# Motherboard_Rev_A.net
KiCad netlist of a schematic drawn in EAGLE
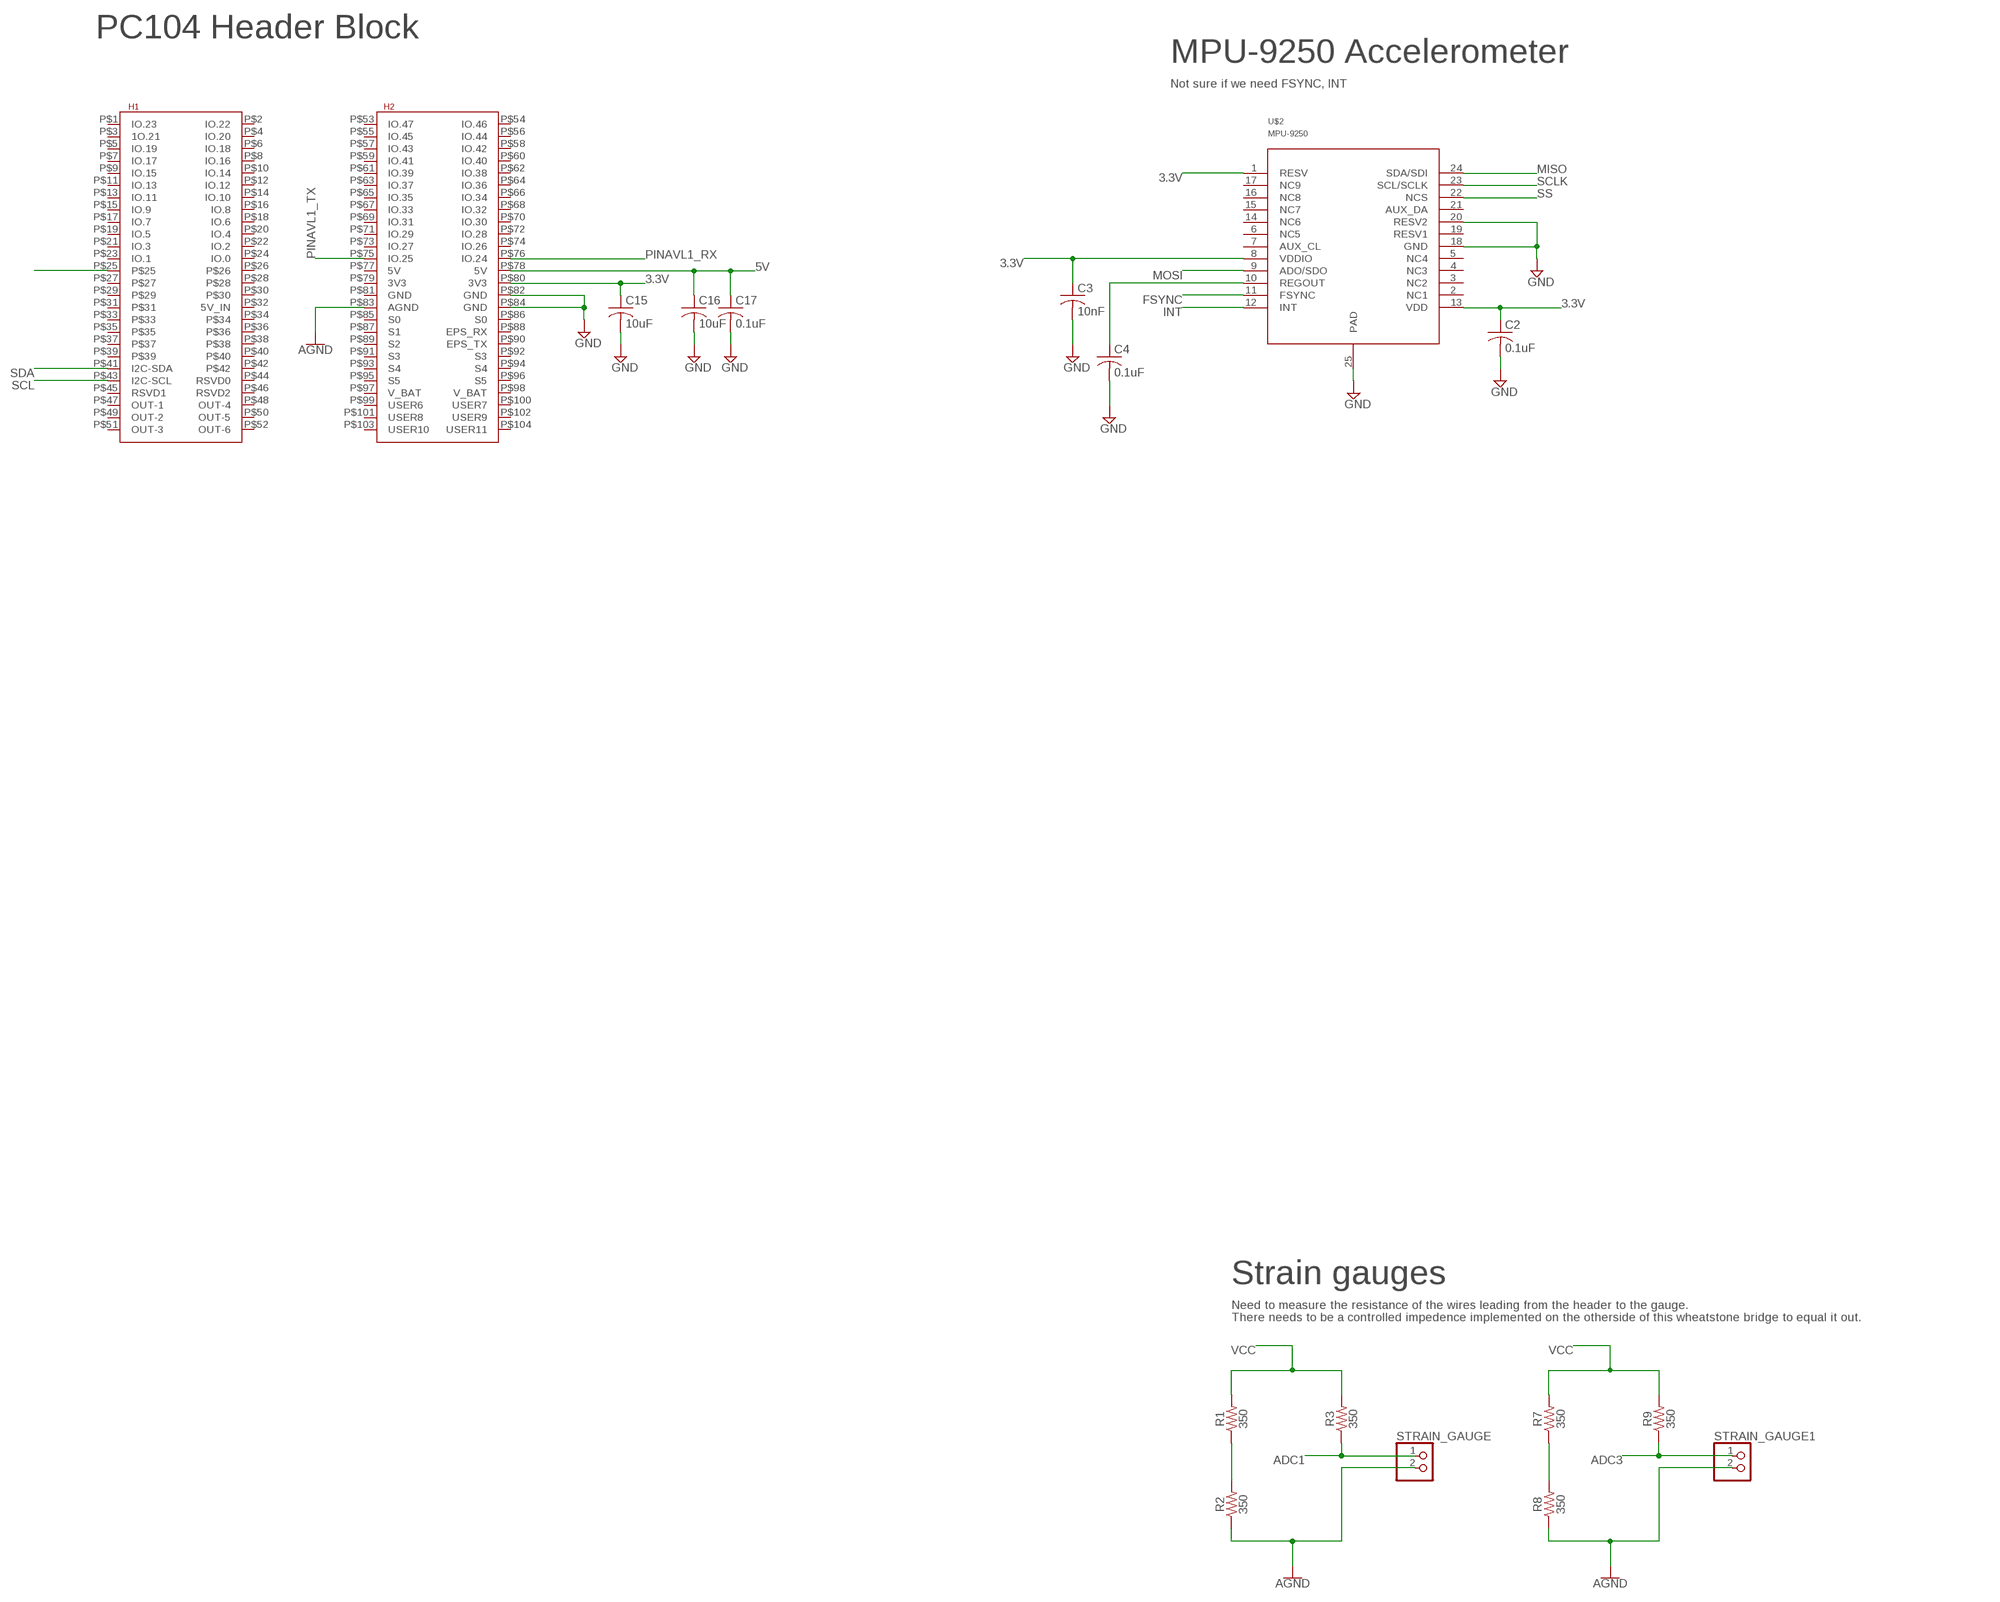
[diagram p0: schematic, sheet 1, part 1 of 2]
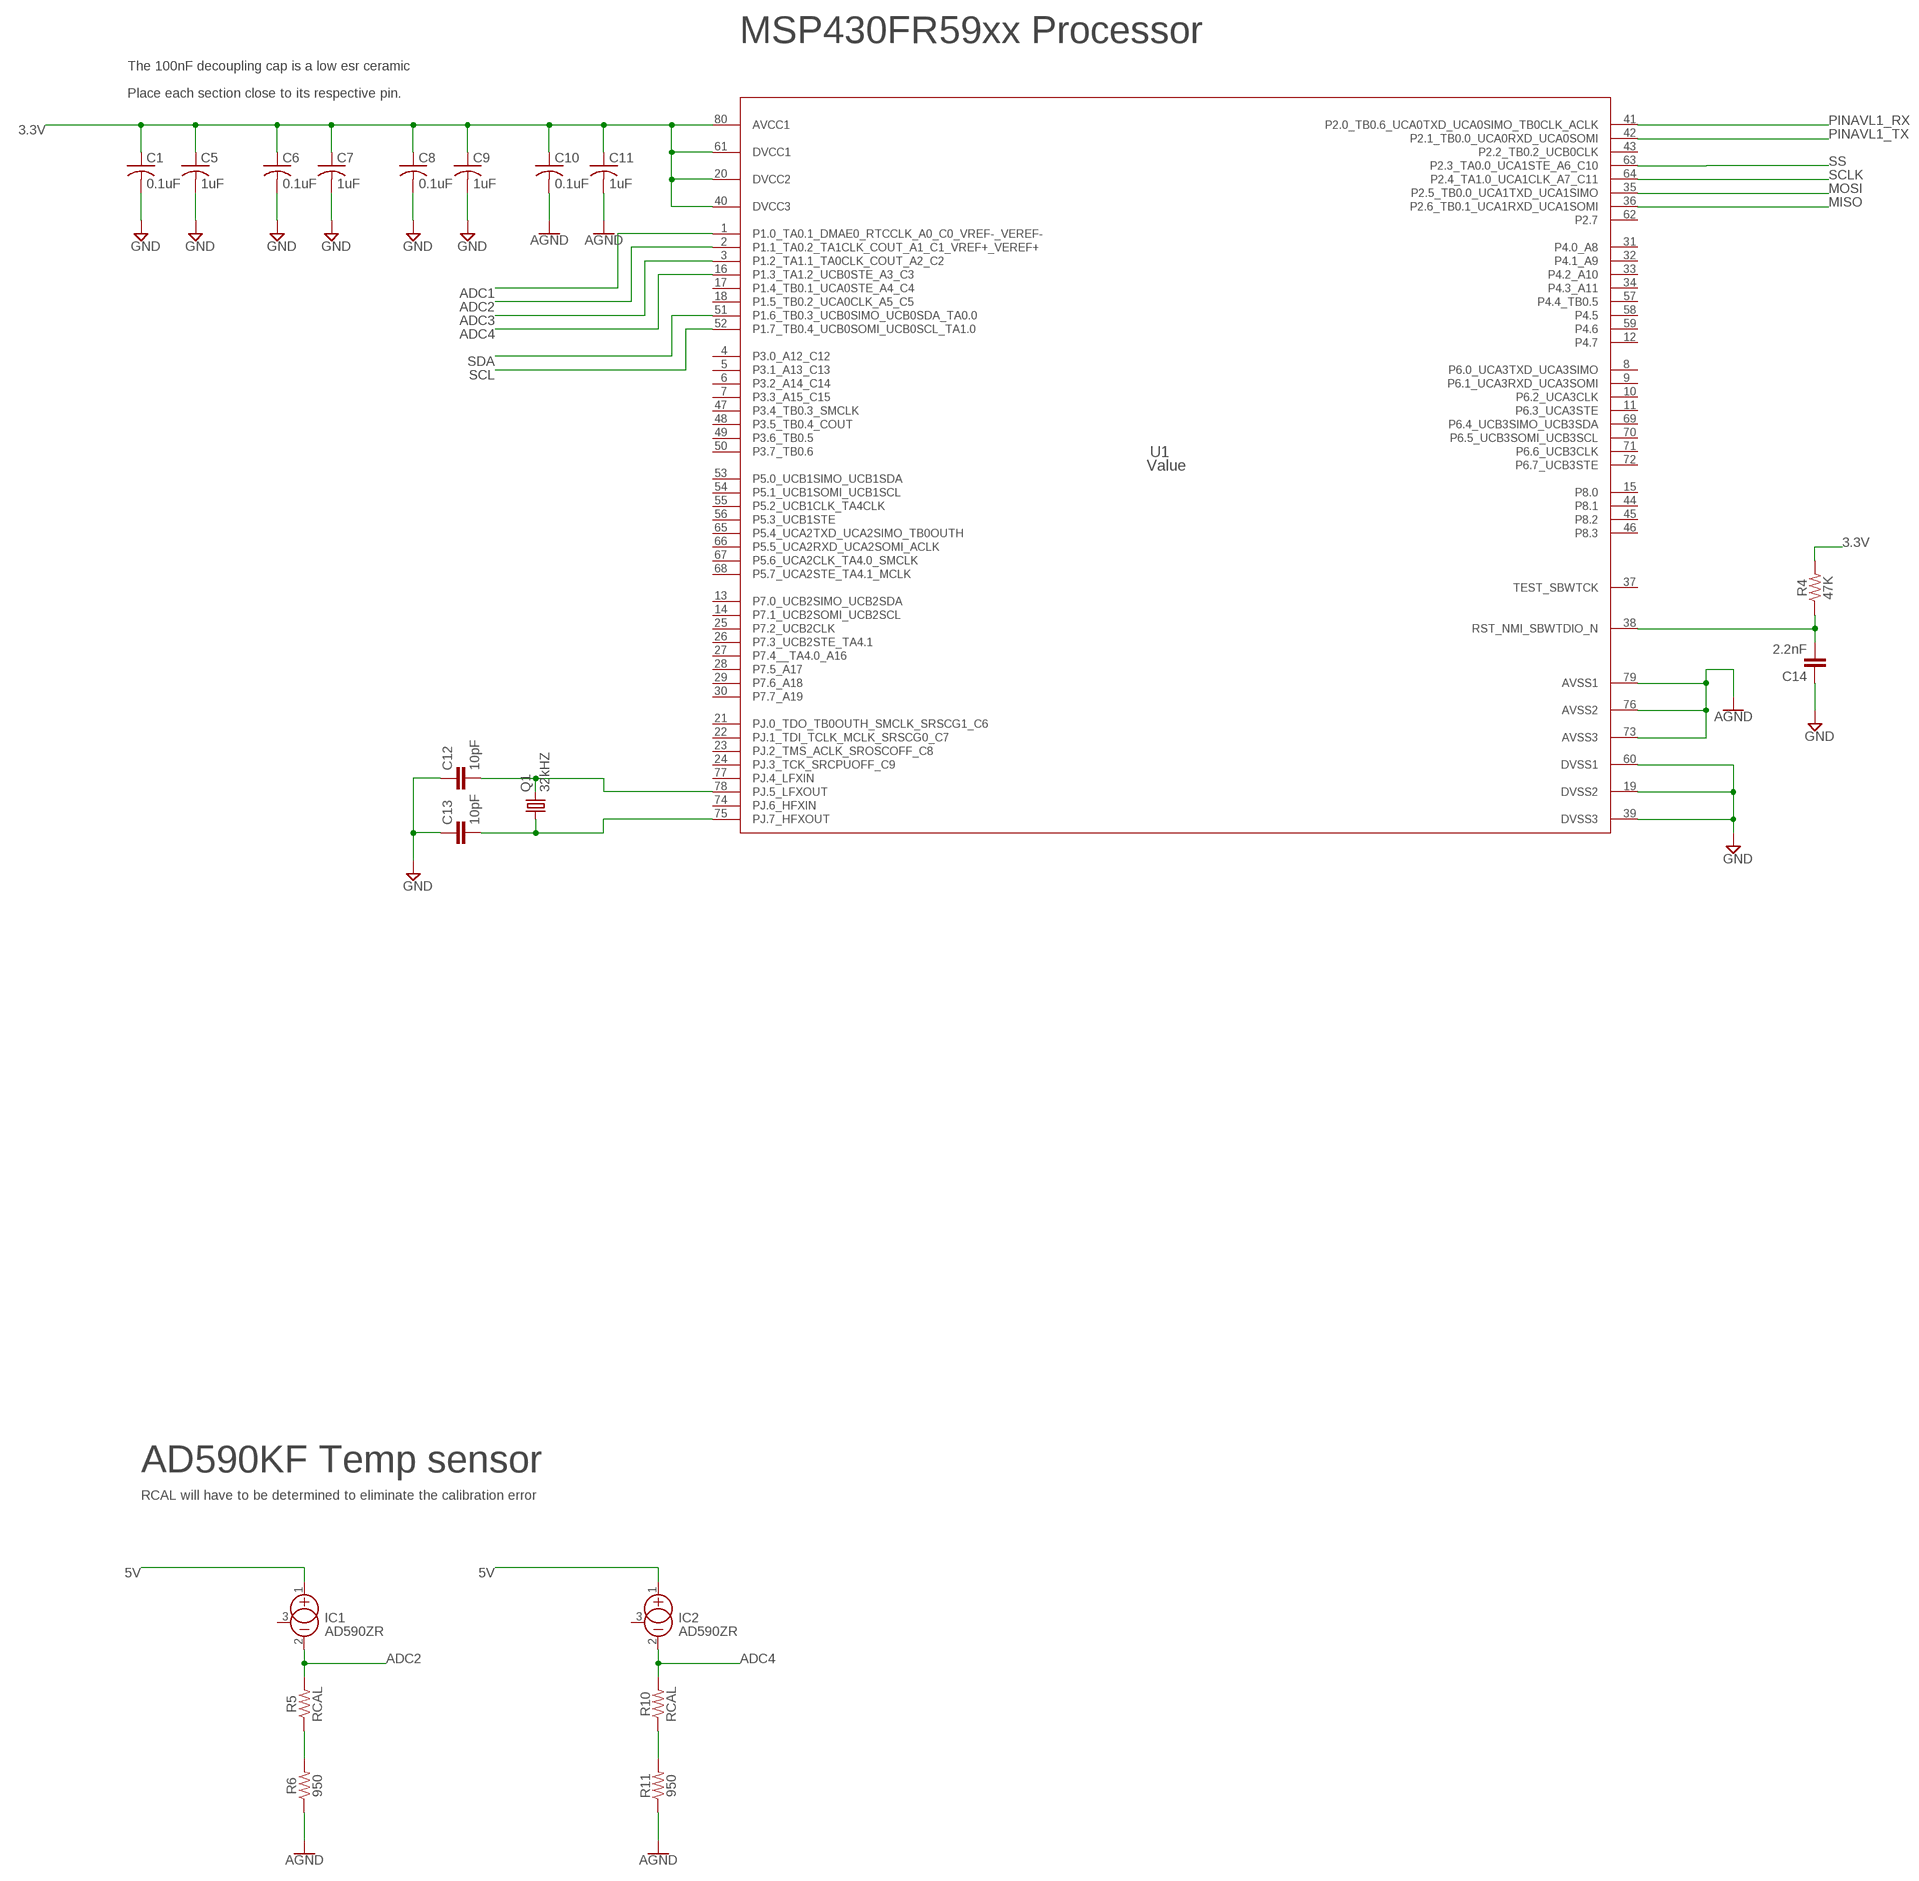
[diagram p1: schematic, sheet 1, part 2 of 2]

(export (version "E")
  (design (tool "Eeschema 10.0.6"))
  (components
    (comp (ref "C1")
      (value "0.1uF")
      (footprint "eagle-import:C0603")
      (libsource (lib "eagle-import") (part "C-USC0603"))
    )
    (comp (ref "C2")
      (value "0.1uF")
      (footprint "eagle-import:C0603")
      (libsource (lib "eagle-import") (part "C-USC0603"))
    )
    (comp (ref "C3")
      (value "10nF")
      (footprint "eagle-import:C0603")
      (libsource (lib "eagle-import") (part "C-USC0603"))
    )
    (comp (ref "C4")
      (value "0.1uF")
      (footprint "eagle-import:C0603")
      (libsource (lib "eagle-import") (part "C-USC0603"))
    )
    (comp (ref "C5")
      (value "1uF")
      (footprint "eagle-import:C0603")
      (libsource (lib "eagle-import") (part "C-USC0603"))
    )
    (comp (ref "C6")
      (value "0.1uF")
      (footprint "eagle-import:C0603")
      (libsource (lib "eagle-import") (part "C-USC0603"))
    )
    (comp (ref "C7")
      (value "1uF")
      (footprint "eagle-import:C0603")
      (libsource (lib "eagle-import") (part "C-USC0603"))
    )
    (comp (ref "C8")
      (value "0.1uF")
      (footprint "eagle-import:C0603")
      (libsource (lib "eagle-import") (part "C-USC0603"))
    )
    (comp (ref "C9")
      (value "1uF")
      (footprint "eagle-import:C0603")
      (libsource (lib "eagle-import") (part "C-USC0603"))
    )
    (comp (ref "C10")
      (value "0.1uF")
      (footprint "eagle-import:C0603")
      (libsource (lib "eagle-import") (part "C-USC0603"))
    )
    (comp (ref "C11")
      (value "1uF")
      (footprint "eagle-import:C0603")
      (libsource (lib "eagle-import") (part "C-USC0603"))
    )
    (comp (ref "C12")
      (value "10pF")
      (footprint "eagle-import:0603")
      (libsource (lib "eagle-import") (part "560PF-0603-50V-5%"))
    )
    (comp (ref "C13")
      (value "10pF")
      (footprint "eagle-import:0603")
      (libsource (lib "eagle-import") (part "560PF-0603-50V-5%"))
    )
    (comp (ref "C14")
      (value "2.2nF")
      (footprint "eagle-import:0603")
      (libsource (lib "eagle-import") (part "560PF-0603-50V-5%"))
    )
    (comp (ref "C15")
      (value "10uF")
      (footprint "eagle-import:C0603")
      (libsource (lib "eagle-import") (part "C-USC0603"))
    )
    (comp (ref "C16")
      (value "10uF")
      (footprint "eagle-import:C0603")
      (libsource (lib "eagle-import") (part "C-USC0603"))
    )
    (comp (ref "C17")
      (value "0.1uF")
      (footprint "eagle-import:C0603")
      (libsource (lib "eagle-import") (part "C-USC0603"))
    )
    (comp (ref "IC1")
      (value "AD590ZR")
      (footprint "eagle-import:TO92")
      (libsource (lib "eagle-import") (part "AD590ZR"))
    )
    (comp (ref "IC2")
      (value "AD590ZR")
      (footprint "eagle-import:TO92")
      (libsource (lib "eagle-import") (part "AD590ZR"))
    )
    (comp (ref "Q1")
      (value "32kHZ")
      (footprint "eagle-import:HC49_S")
      (libsource (lib "eagle-import") (part "CRYSTALHC49S"))
    )
    (comp (ref "R1")
      (value "350")
      (footprint "eagle-import:0603")
      (libsource (lib "eagle-import") (part "12.1KOHM-0603-1/10W-1%"))
    )
    (comp (ref "R2")
      (value "350")
      (footprint "eagle-import:0603")
      (libsource (lib "eagle-import") (part "12.1KOHM-0603-1/10W-1%"))
    )
    (comp (ref "R3")
      (value "350")
      (footprint "eagle-import:0603")
      (libsource (lib "eagle-import") (part "12.1KOHM-0603-1/10W-1%"))
    )
    (comp (ref "R4")
      (value "47K")
      (footprint "eagle-import:0603")
      (libsource (lib "eagle-import") (part "12.1KOHM-0603-1/10W-1%"))
    )
    (comp (ref "R5")
      (value "RCAL")
      (footprint "eagle-import:0603")
      (libsource (lib "eagle-import") (part "12.1KOHM-0603-1/10W-1%"))
    )
    (comp (ref "R6")
      (value "950")
      (footprint "eagle-import:0603")
      (libsource (lib "eagle-import") (part "12.1KOHM-0603-1/10W-1%"))
    )
    (comp (ref "R7")
      (value "350")
      (footprint "eagle-import:0603")
      (libsource (lib "eagle-import") (part "12.1KOHM-0603-1/10W-1%"))
    )
    (comp (ref "R8")
      (value "350")
      (footprint "eagle-import:0603")
      (libsource (lib "eagle-import") (part "12.1KOHM-0603-1/10W-1%"))
    )
    (comp (ref "R9")
      (value "350")
      (footprint "eagle-import:0603")
      (libsource (lib "eagle-import") (part "12.1KOHM-0603-1/10W-1%"))
    )
    (comp (ref "R10")
      (value "RCAL")
      (footprint "eagle-import:0603")
      (libsource (lib "eagle-import") (part "12.1KOHM-0603-1/10W-1%"))
    )
    (comp (ref "R11")
      (value "950")
      (footprint "eagle-import:0603")
      (libsource (lib "eagle-import") (part "12.1KOHM-0603-1/10W-1%"))
    )
    (comp (ref "STRAIN_GAUGE")
      (value "PINHD-1X2")
      (footprint "eagle-import:1X02")
      (libsource (lib "eagle-import") (part "PINHD-1X2"))
    )
    (comp (ref "STRAIN_GAUGE1")
      (value "PINHD-1X2")
      (footprint "eagle-import:1X02")
      (libsource (lib "eagle-import") (part "PINHD-1X2"))
    )
    (comp (ref "U$1")
      (value "PC104")
      (footprint "eagle-import:PC104")
      (libsource (lib "eagle-import") (part "PC104"))
    )
    (comp (ref "U$2")
      (value "MPU-9250")
      (footprint "eagle-import:LEAD-QFN24")
      (libsource (lib "eagle-import") (part "MPU-9250"))
    )
    (comp (ref "U1")
      (value "Value")
      (footprint "eagle-import:PN0080A_N")
      (fields
        (field (name "MANUFACTURER") "Texas Instruments")
        (field (name "PARTNUMBER") "MSP430FR5994IPNR")
      )
      (libsource (lib "eagle-import") (part "MSP430FR5994IPNR"))
    )
  )
  (nets
    (net (code "1") (name "3.3V") (class "Default")
      (node (ref "C1") (pin "1") (pinfunction "1_1") (pintype "passive"))
      (node (ref "C10") (pin "1") (pinfunction "1_1") (pintype "passive"))
      (node (ref "C11") (pin "1") (pinfunction "1_1") (pintype "passive"))
      (node (ref "C15") (pin "1") (pinfunction "1_1") (pintype "passive"))
      (node (ref "C2") (pin "1") (pinfunction "1_1") (pintype "passive"))
      (node (ref "C3") (pin "1") (pinfunction "1_1") (pintype "passive"))
      (node (ref "C5") (pin "1") (pinfunction "1_1") (pintype "passive"))
      (node (ref "C6") (pin "1") (pinfunction "1_1") (pintype "passive"))
      (node (ref "C7") (pin "1") (pinfunction "1_1") (pintype "passive"))
      (node (ref "C8") (pin "1") (pinfunction "1_1") (pintype "passive"))
      (node (ref "C9") (pin "1") (pinfunction "1_1") (pintype "passive"))
      (node (ref "R4") (pin "2") (pinfunction "2_2") (pintype "passive"))
      (node (ref "U$1") (pin "P$80") (pinfunction "3V3_P$80") (pintype "bidirectional"))
      (node (ref "U$2") (pin "1") (pinfunction "RESV_1") (pintype "bidirectional"))
      (node (ref "U$2") (pin "13") (pinfunction "VDD_13") (pintype "bidirectional"))
      (node (ref "U$2") (pin "8") (pinfunction "VDDIO_8") (pintype "bidirectional"))
      (node (ref "U1") (pin "20") (pinfunction "DVCC2_20") (pintype "power_in"))
      (node (ref "U1") (pin "40") (pinfunction "DVCC3_40") (pintype "power_in"))
      (node (ref "U1") (pin "61") (pinfunction "DVCC1_61") (pintype "power_in"))
      (node (ref "U1") (pin "80") (pinfunction "AVCC1_80") (pintype "power_in"))
    )
    (net (code "2") (name "5V") (class "Default")
      (node (ref "C16") (pin "1") (pinfunction "1_1") (pintype "passive"))
      (node (ref "C17") (pin "1") (pinfunction "1_1") (pintype "passive"))
      (node (ref "IC1") (pin "1") (pinfunction "+_1") (pintype "input"))
      (node (ref "IC2") (pin "1") (pinfunction "+_1") (pintype "input"))
      (node (ref "U$1") (pin "P$78") (pinfunction "5V_P$78") (pintype "bidirectional"))
    )
    (net (code "3") (name "ADC1") (class "Default")
      (node (ref "R3") (pin "1") (pinfunction "1_1") (pintype "passive"))
      (node (ref "STRAIN_GAUGE") (pin "1") (pinfunction "1_1") (pintype "passive"))
      (node (ref "U1") (pin "1") (pinfunction "P1.0_TA0.1_DMAE0_RTCCLK_A0_C0_VREF-_VEREF-_1") (pintype "bidirectional"))
    )
    (net (code "4") (name "ADC2") (class "Default")
      (node (ref "IC1") (pin "2") (pinfunction "-_2") (pintype "input"))
      (node (ref "R5") (pin "2") (pinfunction "2_2") (pintype "passive"))
      (node (ref "U1") (pin "2") (pinfunction "P1.1_TA0.2_TA1CLK_COUT_A1_C1_VREF+_VEREF+_2") (pintype "bidirectional"))
    )
    (net (code "5") (name "ADC3") (class "Default")
      (node (ref "R9") (pin "1") (pinfunction "1_1") (pintype "passive"))
      (node (ref "STRAIN_GAUGE1") (pin "1") (pinfunction "1_1") (pintype "passive"))
      (node (ref "U1") (pin "3") (pinfunction "P1.2_TA1.1_TA0CLK_COUT_A2_C2_3") (pintype "bidirectional"))
    )
    (net (code "6") (name "ADC4") (class "Default")
      (node (ref "IC2") (pin "2") (pinfunction "-_2") (pintype "input"))
      (node (ref "R10") (pin "2") (pinfunction "2_2") (pintype "passive"))
      (node (ref "U1") (pin "16") (pinfunction "P1.3_TA1.2_UCB0STE_A3_C3_16") (pintype "bidirectional"))
    )
    (net (code "7") (name "AGND") (class "Default")
      (node (ref "C10") (pin "2") (pinfunction "2_2") (pintype "passive"))
      (node (ref "C11") (pin "2") (pinfunction "2_2") (pintype "passive"))
      (node (ref "R11") (pin "1") (pinfunction "1_1") (pintype "passive"))
      (node (ref "R2") (pin "1") (pinfunction "1_1") (pintype "passive"))
      (node (ref "R6") (pin "1") (pinfunction "1_1") (pintype "passive"))
      (node (ref "R8") (pin "1") (pinfunction "1_1") (pintype "passive"))
      (node (ref "STRAIN_GAUGE") (pin "2") (pinfunction "2_2") (pintype "passive"))
      (node (ref "STRAIN_GAUGE1") (pin "2") (pinfunction "2_2") (pintype "passive"))
      (node (ref "U$1") (pin "P$83") (pinfunction "AGND_P$83") (pintype "bidirectional"))
      (node (ref "U1") (pin "73") (pinfunction "AVSS3_73") (pintype "power_in"))
      (node (ref "U1") (pin "76") (pinfunction "AVSS2_76") (pintype "power_in"))
      (node (ref "U1") (pin "79") (pinfunction "AVSS1_79") (pintype "power_in"))
    )
    (net (code "8") (name "FSYNC") (class "Default")
      (node (ref "U$2") (pin "11") (pinfunction "FSYNC_11") (pintype "bidirectional"))
    )
    (net (code "9") (name "GND") (class "Default")
      (node (ref "C1") (pin "2") (pinfunction "2_2") (pintype "passive"))
      (node (ref "C12") (pin "1") (pinfunction "1_1") (pintype "passive"))
      (node (ref "C13") (pin "1") (pinfunction "1_1") (pintype "passive"))
      (node (ref "C14") (pin "1") (pinfunction "1_1") (pintype "passive"))
      (node (ref "C15") (pin "2") (pinfunction "2_2") (pintype "passive"))
      (node (ref "C16") (pin "2") (pinfunction "2_2") (pintype "passive"))
      (node (ref "C17") (pin "2") (pinfunction "2_2") (pintype "passive"))
      (node (ref "C2") (pin "2") (pinfunction "2_2") (pintype "passive"))
      (node (ref "C3") (pin "2") (pinfunction "2_2") (pintype "passive"))
      (node (ref "C4") (pin "2") (pinfunction "2_2") (pintype "passive"))
      (node (ref "C5") (pin "2") (pinfunction "2_2") (pintype "passive"))
      (node (ref "C6") (pin "2") (pinfunction "2_2") (pintype "passive"))
      (node (ref "C7") (pin "2") (pinfunction "2_2") (pintype "passive"))
      (node (ref "C8") (pin "2") (pinfunction "2_2") (pintype "passive"))
      (node (ref "C9") (pin "2") (pinfunction "2_2") (pintype "passive"))
      (node (ref "U$1") (pin "P$82") (pinfunction "GND_P$82") (pintype "bidirectional"))
      (node (ref "U$1") (pin "P$84") (pinfunction "GND_P$84") (pintype "bidirectional"))
      (node (ref "U$2") (pin "18") (pinfunction "GND_18") (pintype "bidirectional"))
      (node (ref "U$2") (pin "20") (pinfunction "RESV2_20") (pintype "bidirectional"))
      (node (ref "U$2") (pin "25") (pinfunction "PAD_25") (pintype "bidirectional"))
      (node (ref "U1") (pin "19") (pinfunction "DVSS2_19") (pintype "power_in"))
      (node (ref "U1") (pin "39") (pinfunction "DVSS3_39") (pintype "power_in"))
      (node (ref "U1") (pin "60") (pinfunction "DVSS1_60") (pintype "power_in"))
    )
    (net (code "10") (name "INT") (class "Default")
      (node (ref "U$2") (pin "12") (pinfunction "INT_12") (pintype "bidirectional"))
    )
    (net (code "11") (name "MISO") (class "Default")
      (node (ref "U$2") (pin "24") (pinfunction "SDA/SDI_24") (pintype "bidirectional"))
      (node (ref "U1") (pin "36") (pinfunction "P2.6_TB0.1_UCA1RXD_UCA1SOMI_36") (pintype "bidirectional"))
    )
    (net (code "12") (name "MOSI") (class "Default")
      (node (ref "U$2") (pin "9") (pinfunction "ADO/SDO_9") (pintype "bidirectional"))
      (node (ref "U1") (pin "35") (pinfunction "P2.5_TB0.0_UCA1TXD_UCA1SIMO_35") (pintype "bidirectional"))
    )
    (net (code "13") (name "Net-(R1-Pad1)") (class "Default")
      (node (ref "R1") (pin "1") (pinfunction "1_1") (pintype "passive"))
      (node (ref "R2") (pin "2") (pinfunction "2_2") (pintype "passive"))
    )
    (net (code "14") (name "Net-(R5-Pad1)") (class "Default")
      (node (ref "R5") (pin "1") (pinfunction "1_1") (pintype "passive"))
      (node (ref "R6") (pin "2") (pinfunction "2_2") (pintype "passive"))
    )
    (net (code "15") (name "Net-(R7-Pad1)") (class "Default")
      (node (ref "R7") (pin "1") (pinfunction "1_1") (pintype "passive"))
      (node (ref "R8") (pin "2") (pinfunction "2_2") (pintype "passive"))
    )
    (net (code "16") (name "Net-(R10-Pad1)") (class "Default")
      (node (ref "R10") (pin "1") (pinfunction "1_1") (pintype "passive"))
      (node (ref "R11") (pin "2") (pinfunction "2_2") (pintype "passive"))
    )
    (net (code "17") (name "Net-(U$2-REGOUT)") (class "Default")
      (node (ref "C4") (pin "1") (pinfunction "1_1") (pintype "passive"))
      (node (ref "U$2") (pin "10") (pinfunction "REGOUT_10") (pintype "bidirectional"))
    )
    (net (code "18") (name "Net-(U1-PJ.5_LFXOUT)") (class "Default")
      (node (ref "C12") (pin "2") (pinfunction "2_2") (pintype "passive"))
      (node (ref "Q1") (pin "2") (pinfunction "2_2") (pintype "passive"))
      (node (ref "U1") (pin "78") (pinfunction "PJ.5_LFXOUT_78") (pintype "bidirectional"))
    )
    (net (code "19") (name "Net-(U1-PJ.7_HFXOUT)") (class "Default")
      (node (ref "C13") (pin "2") (pinfunction "2_2") (pintype "passive"))
      (node (ref "Q1") (pin "1") (pinfunction "1_1") (pintype "passive"))
      (node (ref "U1") (pin "75") (pinfunction "PJ.7_HFXOUT_75") (pintype "bidirectional"))
    )
    (net (code "20") (name "Net-(U1-RST_NMI_SBWTDIO_N)") (class "Default")
      (node (ref "C14") (pin "2") (pinfunction "2_2") (pintype "passive"))
      (node (ref "R4") (pin "1") (pinfunction "1_1") (pintype "passive"))
      (node (ref "U1") (pin "38") (pinfunction "RST_NMI_SBWTDIO_N_38") (pintype "bidirectional"))
    )
    (net (code "21") (name "PINAVL1_RX") (class "Default")
      (node (ref "U$1") (pin "P$76") (pinfunction "IO.24_P$76") (pintype "bidirectional"))
      (node (ref "U1") (pin "41") (pinfunction "P2.0_TB0.6_UCA0TXD_UCA0SIMO_TB0CLK_ACLK_41") (pintype "bidirectional"))
    )
    (net (code "22") (name "PINAVL1_TX") (class "Default")
      (node (ref "U$1") (pin "P$75") (pinfunction "IO.25_P$75") (pintype "bidirectional"))
      (node (ref "U1") (pin "42") (pinfunction "P2.1_TB0.0_UCA0RXD_UCA0SOMI_42") (pintype "bidirectional"))
    )
    (net (code "23") (name "SCL") (class "Default")
      (node (ref "U$1") (pin "P$43") (pinfunction "I2C-SCL_P$43") (pintype "bidirectional"))
      (node (ref "U1") (pin "52") (pinfunction "P1.7_TB0.4_UCB0SOMI_UCB0SCL_TA1.0_52") (pintype "bidirectional"))
    )
    (net (code "24") (name "SCLK") (class "Default")
      (node (ref "U$2") (pin "23") (pinfunction "SCL/SCLK_23") (pintype "bidirectional"))
      (node (ref "U1") (pin "64") (pinfunction "P2.4_TA1.0_UCA1CLK_A7_C11_64") (pintype "bidirectional"))
    )
    (net (code "25") (name "SDA") (class "Default")
      (node (ref "U$1") (pin "P$41") (pinfunction "I2C-SDA_P$41") (pintype "bidirectional"))
      (node (ref "U1") (pin "51") (pinfunction "P1.6_TB0.3_UCB0SIMO_UCB0SDA_TA0.0_51") (pintype "bidirectional"))
    )
    (net (code "26") (name "SS") (class "Default")
      (node (ref "U$2") (pin "22") (pinfunction "NCS_22") (pintype "bidirectional"))
      (node (ref "U1") (pin "63") (pinfunction "P2.3_TA0.0_UCA1STE_A6_C10_63") (pintype "bidirectional"))
    )
    (net (code "27") (name "VCC") (class "Default")
      (node (ref "R1") (pin "2") (pinfunction "2_2") (pintype "passive"))
      (node (ref "R3") (pin "2") (pinfunction "2_2") (pintype "passive"))
      (node (ref "R7") (pin "2") (pinfunction "2_2") (pintype "passive"))
      (node (ref "R9") (pin "2") (pinfunction "2_2") (pintype "passive"))
    )
    (net (code "28") (name "unconnected-(IC1-CAN-Pad3)") (class "Default")
      (node (ref "IC1") (pin "3") (pinfunction "CAN_3") (pintype "passive"))
    )
    (net (code "29") (name "unconnected-(IC2-CAN-Pad3)") (class "Default")
      (node (ref "IC2") (pin "3") (pinfunction "CAN_3") (pintype "passive"))
    )
    (net (code "30") (name "unconnected-(U$1-1O.21-PadP$3)") (class "Default")
      (node (ref "U$1") (pin "P$3") (pinfunction "1O.21_P$3") (pintype "bidirectional"))
    )
    (net (code "31") (name "unconnected-(U$1-3V3-PadP$79)") (class "Default")
      (node (ref "U$1") (pin "P$79") (pinfunction "3V3_P$79") (pintype "bidirectional"))
    )
    (net (code "32") (name "unconnected-(U$1-5V-PadP$77)") (class "Default")
      (node (ref "U$1") (pin "P$77") (pinfunction "5V_P$77") (pintype "bidirectional"))
    )
    (net (code "33") (name "unconnected-(U$1-5V_IN-PadP$32)") (class "Default")
      (node (ref "U$1") (pin "P$32") (pinfunction "5V_IN_P$32") (pintype "bidirectional"))
    )
    (net (code "34") (name "unconnected-(U$1-EPS_RX-PadP$88)") (class "Default")
      (node (ref "U$1") (pin "P$88") (pinfunction "EPS_RX_P$88") (pintype "bidirectional"))
    )
    (net (code "35") (name "unconnected-(U$1-EPS_TX-PadP$90)") (class "Default")
      (node (ref "U$1") (pin "P$90") (pinfunction "EPS_TX_P$90") (pintype "bidirectional"))
    )
    (net (code "36") (name "unconnected-(U$1-GND-PadP$81)") (class "Default")
      (node (ref "U$1") (pin "P$81") (pinfunction "GND_P$81") (pintype "bidirectional"))
    )
    (net (code "37") (name "unconnected-(U$1-IO.0-PadP$24)") (class "Default")
      (node (ref "U$1") (pin "P$24") (pinfunction "IO.0_P$24") (pintype "bidirectional"))
    )
    (net (code "38") (name "unconnected-(U$1-IO.1-PadP$23)") (class "Default")
      (node (ref "U$1") (pin "P$23") (pinfunction "IO.1_P$23") (pintype "bidirectional"))
    )
    (net (code "39") (name "unconnected-(U$1-IO.2-PadP$22)") (class "Default")
      (node (ref "U$1") (pin "P$22") (pinfunction "IO.2_P$22") (pintype "bidirectional"))
    )
    (net (code "40") (name "unconnected-(U$1-IO.3-PadP$21)") (class "Default")
      (node (ref "U$1") (pin "P$21") (pinfunction "IO.3_P$21") (pintype "bidirectional"))
    )
    (net (code "41") (name "unconnected-(U$1-IO.4-PadP$20)") (class "Default")
      (node (ref "U$1") (pin "P$20") (pinfunction "IO.4_P$20") (pintype "bidirectional"))
    )
    (net (code "42") (name "unconnected-(U$1-IO.5-PadP$19)") (class "Default")
      (node (ref "U$1") (pin "P$19") (pinfunction "IO.5_P$19") (pintype "bidirectional"))
    )
    (net (code "43") (name "unconnected-(U$1-IO.6-PadP$18)") (class "Default")
      (node (ref "U$1") (pin "P$18") (pinfunction "IO.6_P$18") (pintype "bidirectional"))
    )
    (net (code "44") (name "unconnected-(U$1-IO.7-PadP$17)") (class "Default")
      (node (ref "U$1") (pin "P$17") (pinfunction "IO.7_P$17") (pintype "bidirectional"))
    )
    (net (code "45") (name "unconnected-(U$1-IO.8-PadP$16)") (class "Default")
      (node (ref "U$1") (pin "P$16") (pinfunction "IO.8_P$16") (pintype "bidirectional"))
    )
    (net (code "46") (name "unconnected-(U$1-IO.9-PadP$15)") (class "Default")
      (node (ref "U$1") (pin "P$15") (pinfunction "IO.9_P$15") (pintype "bidirectional"))
    )
    (net (code "47") (name "unconnected-(U$1-IO.10-PadP$14)") (class "Default")
      (node (ref "U$1") (pin "P$14") (pinfunction "IO.10_P$14") (pintype "bidirectional"))
    )
    (net (code "48") (name "unconnected-(U$1-IO.11-PadP$13)") (class "Default")
      (node (ref "U$1") (pin "P$13") (pinfunction "IO.11_P$13") (pintype "bidirectional"))
    )
    (net (code "49") (name "unconnected-(U$1-IO.12-PadP$12)") (class "Default")
      (node (ref "U$1") (pin "P$12") (pinfunction "IO.12_P$12") (pintype "bidirectional"))
    )
    (net (code "50") (name "unconnected-(U$1-IO.13-PadP$11)") (class "Default")
      (node (ref "U$1") (pin "P$11") (pinfunction "IO.13_P$11") (pintype "bidirectional"))
    )
    (net (code "51") (name "unconnected-(U$1-IO.14-PadP$10)") (class "Default")
      (node (ref "U$1") (pin "P$10") (pinfunction "IO.14_P$10") (pintype "bidirectional"))
    )
    (net (code "52") (name "unconnected-(U$1-IO.15-PadP$9)") (class "Default")
      (node (ref "U$1") (pin "P$9") (pinfunction "IO.15_P$9") (pintype "bidirectional"))
    )
    (net (code "53") (name "unconnected-(U$1-IO.16-PadP$8)") (class "Default")
      (node (ref "U$1") (pin "P$8") (pinfunction "IO.16_P$8") (pintype "bidirectional"))
    )
    (net (code "54") (name "unconnected-(U$1-IO.17-PadP$7)") (class "Default")
      (node (ref "U$1") (pin "P$7") (pinfunction "IO.17_P$7") (pintype "bidirectional"))
    )
    (net (code "55") (name "unconnected-(U$1-IO.18-PadP$6)") (class "Default")
      (node (ref "U$1") (pin "P$6") (pinfunction "IO.18_P$6") (pintype "bidirectional"))
    )
    (net (code "56") (name "unconnected-(U$1-IO.19-PadP$5)") (class "Default")
      (node (ref "U$1") (pin "P$5") (pinfunction "IO.19_P$5") (pintype "bidirectional"))
    )
    (net (code "57") (name "unconnected-(U$1-IO.20-PadP$4)") (class "Default")
      (node (ref "U$1") (pin "P$4") (pinfunction "IO.20_P$4") (pintype "bidirectional"))
    )
    (net (code "58") (name "unconnected-(U$1-IO.22-PadP$2)") (class "Default")
      (node (ref "U$1") (pin "P$2") (pinfunction "IO.22_P$2") (pintype "bidirectional"))
    )
    (net (code "59") (name "unconnected-(U$1-IO.23-PadP$1)") (class "Default")
      (node (ref "U$1") (pin "P$1") (pinfunction "IO.23_P$1") (pintype "bidirectional"))
    )
    (net (code "60") (name "unconnected-(U$1-IO.26-PadP$74)") (class "Default")
      (node (ref "U$1") (pin "P$74") (pinfunction "IO.26_P$74") (pintype "bidirectional"))
    )
    (net (code "61") (name "unconnected-(U$1-IO.27-PadP$73)") (class "Default")
      (node (ref "U$1") (pin "P$73") (pinfunction "IO.27_P$73") (pintype "bidirectional"))
    )
    (net (code "62") (name "unconnected-(U$1-IO.28-PadP$72)") (class "Default")
      (node (ref "U$1") (pin "P$72") (pinfunction "IO.28_P$72") (pintype "bidirectional"))
    )
    (net (code "63") (name "unconnected-(U$1-IO.29-PadP$71)") (class "Default")
      (node (ref "U$1") (pin "P$71") (pinfunction "IO.29_P$71") (pintype "bidirectional"))
    )
    (net (code "64") (name "unconnected-(U$1-IO.30-PadP$70)") (class "Default")
      (node (ref "U$1") (pin "P$70") (pinfunction "IO.30_P$70") (pintype "bidirectional"))
    )
    (net (code "65") (name "unconnected-(U$1-IO.31-PadP$69)") (class "Default")
      (node (ref "U$1") (pin "P$69") (pinfunction "IO.31_P$69") (pintype "bidirectional"))
    )
    (net (code "66") (name "unconnected-(U$1-IO.32-PadP$68)") (class "Default")
      (node (ref "U$1") (pin "P$68") (pinfunction "IO.32_P$68") (pintype "bidirectional"))
    )
    (net (code "67") (name "unconnected-(U$1-IO.33-PadP$67)") (class "Default")
      (node (ref "U$1") (pin "P$67") (pinfunction "IO.33_P$67") (pintype "bidirectional"))
    )
    (net (code "68") (name "unconnected-(U$1-IO.34-PadP$66)") (class "Default")
      (node (ref "U$1") (pin "P$66") (pinfunction "IO.34_P$66") (pintype "bidirectional"))
    )
    (net (code "69") (name "unconnected-(U$1-IO.35-PadP$65)") (class "Default")
      (node (ref "U$1") (pin "P$65") (pinfunction "IO.35_P$65") (pintype "bidirectional"))
    )
    (net (code "70") (name "unconnected-(U$1-IO.36-PadP$64)") (class "Default")
      (node (ref "U$1") (pin "P$64") (pinfunction "IO.36_P$64") (pintype "bidirectional"))
    )
    (net (code "71") (name "unconnected-(U$1-IO.37-PadP$63)") (class "Default")
      (node (ref "U$1") (pin "P$63") (pinfunction "IO.37_P$63") (pintype "bidirectional"))
    )
    (net (code "72") (name "unconnected-(U$1-IO.38-PadP$62)") (class "Default")
      (node (ref "U$1") (pin "P$62") (pinfunction "IO.38_P$62") (pintype "bidirectional"))
    )
    (net (code "73") (name "unconnected-(U$1-IO.39-PadP$61)") (class "Default")
      (node (ref "U$1") (pin "P$61") (pinfunction "IO.39_P$61") (pintype "bidirectional"))
    )
    (net (code "74") (name "unconnected-(U$1-IO.40-PadP$60)") (class "Default")
      (node (ref "U$1") (pin "P$60") (pinfunction "IO.40_P$60") (pintype "bidirectional"))
    )
    (net (code "75") (name "unconnected-(U$1-IO.41-PadP$59)") (class "Default")
      (node (ref "U$1") (pin "P$59") (pinfunction "IO.41_P$59") (pintype "bidirectional"))
    )
    (net (code "76") (name "unconnected-(U$1-IO.42-PadP$58)") (class "Default")
      (node (ref "U$1") (pin "P$58") (pinfunction "IO.42_P$58") (pintype "bidirectional"))
    )
    (net (code "77") (name "unconnected-(U$1-IO.43-PadP$57)") (class "Default")
      (node (ref "U$1") (pin "P$57") (pinfunction "IO.43_P$57") (pintype "bidirectional"))
    )
    (net (code "78") (name "unconnected-(U$1-IO.44-PadP$56)") (class "Default")
      (node (ref "U$1") (pin "P$56") (pinfunction "IO.44_P$56") (pintype "bidirectional"))
    )
    (net (code "79") (name "unconnected-(U$1-IO.45-PadP$55)") (class "Default")
      (node (ref "U$1") (pin "P$55") (pinfunction "IO.45_P$55") (pintype "bidirectional"))
    )
    (net (code "80") (name "unconnected-(U$1-IO.46-PadP$54)") (class "Default")
      (node (ref "U$1") (pin "P$54") (pinfunction "IO.46_P$54") (pintype "bidirectional"))
    )
    (net (code "81") (name "unconnected-(U$1-IO.47-PadP$53)") (class "Default")
      (node (ref "U$1") (pin "P$53") (pinfunction "IO.47_P$53") (pintype "bidirectional"))
    )
    (net (code "82") (name "unconnected-(U$1-OUT-1-PadP$47)") (class "Default")
      (node (ref "U$1") (pin "P$47") (pinfunction "OUT-1_P$47") (pintype "bidirectional"))
    )
    (net (code "83") (name "unconnected-(U$1-OUT-2-PadP$49)") (class "Default")
      (node (ref "U$1") (pin "P$49") (pinfunction "OUT-2_P$49") (pintype "bidirectional"))
    )
    (net (code "84") (name "unconnected-(U$1-OUT-3-PadP$51)") (class "Default")
      (node (ref "U$1") (pin "P$51") (pinfunction "OUT-3_P$51") (pintype "bidirectional"))
    )
    (net (code "85") (name "unconnected-(U$1-OUT-4-PadP$48)") (class "Default")
      (node (ref "U$1") (pin "P$48") (pinfunction "OUT-4_P$48") (pintype "bidirectional"))
    )
    (net (code "86") (name "unconnected-(U$1-OUT-5-PadP$50)") (class "Default")
      (node (ref "U$1") (pin "P$50") (pinfunction "OUT-5_P$50") (pintype "bidirectional"))
    )
    (net (code "87") (name "unconnected-(U$1-OUT-6-PadP$52)") (class "Default")
      (node (ref "U$1") (pin "P$52") (pinfunction "OUT-6_P$52") (pintype "bidirectional"))
    )
    (net (code "88") (name "unconnected-(U$1-PadP$25)") (class "Default")
      (node (ref "U$1") (pin "P$25") (pinfunction "P$25_P$25") (pintype "bidirectional"))
    )
    (net (code "89") (name "unconnected-(U$1-PadP$26)") (class "Default")
      (node (ref "U$1") (pin "P$26") (pinfunction "P$26_P$26") (pintype "bidirectional"))
    )
    (net (code "90") (name "unconnected-(U$1-PadP$27)") (class "Default")
      (node (ref "U$1") (pin "P$27") (pinfunction "P$27_P$27") (pintype "bidirectional"))
    )
    (net (code "91") (name "unconnected-(U$1-PadP$28)") (class "Default")
      (node (ref "U$1") (pin "P$28") (pinfunction "P$28_P$28") (pintype "bidirectional"))
    )
    (net (code "92") (name "unconnected-(U$1-PadP$29)") (class "Default")
      (node (ref "U$1") (pin "P$29") (pinfunction "P$29_P$29") (pintype "bidirectional"))
    )
    (net (code "93") (name "unconnected-(U$1-PadP$30)") (class "Default")
      (node (ref "U$1") (pin "P$30") (pinfunction "P$30_P$30") (pintype "bidirectional"))
    )
    (net (code "94") (name "unconnected-(U$1-PadP$31)") (class "Default")
      (node (ref "U$1") (pin "P$31") (pinfunction "P$31_P$31") (pintype "bidirectional"))
    )
    (net (code "95") (name "unconnected-(U$1-PadP$33)") (class "Default")
      (node (ref "U$1") (pin "P$33") (pinfunction "P$33_P$33") (pintype "bidirectional"))
    )
    (net (code "96") (name "unconnected-(U$1-PadP$34)") (class "Default")
      (node (ref "U$1") (pin "P$34") (pinfunction "P$34_P$34") (pintype "bidirectional"))
    )
    (net (code "97") (name "unconnected-(U$1-PadP$35)") (class "Default")
      (node (ref "U$1") (pin "P$35") (pinfunction "P$35_P$35") (pintype "bidirectional"))
    )
    (net (code "98") (name "unconnected-(U$1-PadP$36)") (class "Default")
      (node (ref "U$1") (pin "P$36") (pinfunction "P$36_P$36") (pintype "bidirectional"))
    )
    (net (code "99") (name "unconnected-(U$1-PadP$37)") (class "Default")
      (node (ref "U$1") (pin "P$37") (pinfunction "P$37_P$37") (pintype "bidirectional"))
    )
    (net (code "100") (name "unconnected-(U$1-PadP$38)") (class "Default")
      (node (ref "U$1") (pin "P$38") (pinfunction "P$38_P$38") (pintype "bidirectional"))
    )
    (net (code "101") (name "unconnected-(U$1-PadP$39)") (class "Default")
      (node (ref "U$1") (pin "P$39") (pinfunction "P$39_P$39") (pintype "bidirectional"))
    )
    (net (code "102") (name "unconnected-(U$1-PadP$40)") (class "Default")
      (node (ref "U$1") (pin "P$40") (pinfunction "P$40_P$40") (pintype "bidirectional"))
    )
    (net (code "103") (name "unconnected-(U$1-PadP$42)") (class "Default")
      (node (ref "U$1") (pin "P$42") (pinfunction "P$42_P$42") (pintype "bidirectional"))
    )
    (net (code "104") (name "unconnected-(U$1-RSVD0-PadP$44)") (class "Default")
      (node (ref "U$1") (pin "P$44") (pinfunction "RSVD0_P$44") (pintype "bidirectional"))
    )
    (net (code "105") (name "unconnected-(U$1-RSVD1-PadP$45)") (class "Default")
      (node (ref "U$1") (pin "P$45") (pinfunction "RSVD1_P$45") (pintype "bidirectional"))
    )
    (net (code "106") (name "unconnected-(U$1-RSVD2-PadP$46)") (class "Default")
      (node (ref "U$1") (pin "P$46") (pinfunction "RSVD2_P$46") (pintype "bidirectional"))
    )
    (net (code "107") (name "unconnected-(U$1-S0-PadP$85)") (class "Default")
      (node (ref "U$1") (pin "P$85") (pinfunction "S0_P$85") (pintype "bidirectional"))
    )
    (net (code "108") (name "unconnected-(U$1-S0-PadP$86)") (class "Default")
      (node (ref "U$1") (pin "P$86") (pinfunction "S0_P$86") (pintype "bidirectional"))
    )
    (net (code "109") (name "unconnected-(U$1-S1-PadP$87)") (class "Default")
      (node (ref "U$1") (pin "P$87") (pinfunction "S1_P$87") (pintype "bidirectional"))
    )
    (net (code "110") (name "unconnected-(U$1-S2-PadP$89)") (class "Default")
      (node (ref "U$1") (pin "P$89") (pinfunction "S2_P$89") (pintype "bidirectional"))
    )
    (net (code "111") (name "unconnected-(U$1-S3-PadP$91)") (class "Default")
      (node (ref "U$1") (pin "P$91") (pinfunction "S3_P$91") (pintype "bidirectional"))
    )
    (net (code "112") (name "unconnected-(U$1-S3-PadP$92)") (class "Default")
      (node (ref "U$1") (pin "P$92") (pinfunction "S3_P$92") (pintype "bidirectional"))
    )
    (net (code "113") (name "unconnected-(U$1-S4-PadP$93)") (class "Default")
      (node (ref "U$1") (pin "P$93") (pinfunction "S4_P$93") (pintype "bidirectional"))
    )
    (net (code "114") (name "unconnected-(U$1-S4-PadP$94)") (class "Default")
      (node (ref "U$1") (pin "P$94") (pinfunction "S4_P$94") (pintype "bidirectional"))
    )
    (net (code "115") (name "unconnected-(U$1-S5-PadP$95)") (class "Default")
      (node (ref "U$1") (pin "P$95") (pinfunction "S5_P$95") (pintype "bidirectional"))
    )
    (net (code "116") (name "unconnected-(U$1-S5-PadP$96)") (class "Default")
      (node (ref "U$1") (pin "P$96") (pinfunction "S5_P$96") (pintype "bidirectional"))
    )
    (net (code "117") (name "unconnected-(U$1-USER6-PadP$99)") (class "Default")
      (node (ref "U$1") (pin "P$99") (pinfunction "USER6_P$99") (pintype "bidirectional"))
    )
    (net (code "118") (name "unconnected-(U$1-USER7-PadP$100)") (class "Default")
      (node (ref "U$1") (pin "P$100") (pinfunction "USER7_P$100") (pintype "bidirectional"))
    )
    (net (code "119") (name "unconnected-(U$1-USER8-PadP$101)") (class "Default")
      (node (ref "U$1") (pin "P$101") (pinfunction "USER8_P$101") (pintype "bidirectional"))
    )
    (net (code "120") (name "unconnected-(U$1-USER9-PadP$102)") (class "Default")
      (node (ref "U$1") (pin "P$102") (pinfunction "USER9_P$102") (pintype "bidirectional"))
    )
    (net (code "121") (name "unconnected-(U$1-USER10-PadP$103)") (class "Default")
      (node (ref "U$1") (pin "P$103") (pinfunction "USER10_P$103") (pintype "bidirectional"))
    )
    (net (code "122") (name "unconnected-(U$1-USER11-PadP$104)") (class "Default")
      (node (ref "U$1") (pin "P$104") (pinfunction "USER11_P$104") (pintype "bidirectional"))
    )
    (net (code "123") (name "unconnected-(U$1-V_BAT-PadP$97)") (class "Default")
      (node (ref "U$1") (pin "P$97") (pinfunction "V_BAT_P$97") (pintype "bidirectional"))
    )
    (net (code "124") (name "unconnected-(U$1-V_BAT-PadP$98)") (class "Default")
      (node (ref "U$1") (pin "P$98") (pinfunction "V_BAT_P$98") (pintype "bidirectional"))
    )
    (net (code "125") (name "unconnected-(U$2-AUX_CL-Pad7)") (class "Default")
      (node (ref "U$2") (pin "7") (pinfunction "AUX_CL_7") (pintype "bidirectional"))
    )
    (net (code "126") (name "unconnected-(U$2-AUX_DA-Pad21)") (class "Default")
      (node (ref "U$2") (pin "21") (pinfunction "AUX_DA_21") (pintype "bidirectional"))
    )
    (net (code "127") (name "unconnected-(U$2-NC1-Pad2)") (class "Default")
      (node (ref "U$2") (pin "2") (pinfunction "NC1_2") (pintype "bidirectional"))
    )
    (net (code "128") (name "unconnected-(U$2-NC2-Pad3)") (class "Default")
      (node (ref "U$2") (pin "3") (pinfunction "NC2_3") (pintype "bidirectional"))
    )
    (net (code "129") (name "unconnected-(U$2-NC3-Pad4)") (class "Default")
      (node (ref "U$2") (pin "4") (pinfunction "NC3_4") (pintype "bidirectional"))
    )
    (net (code "130") (name "unconnected-(U$2-NC4-Pad5)") (class "Default")
      (node (ref "U$2") (pin "5") (pinfunction "NC4_5") (pintype "bidirectional"))
    )
    (net (code "131") (name "unconnected-(U$2-NC5-Pad6)") (class "Default")
      (node (ref "U$2") (pin "6") (pinfunction "NC5_6") (pintype "bidirectional"))
    )
    (net (code "132") (name "unconnected-(U$2-NC6-Pad14)") (class "Default")
      (node (ref "U$2") (pin "14") (pinfunction "NC6_14") (pintype "bidirectional"))
    )
    (net (code "133") (name "unconnected-(U$2-NC7-Pad15)") (class "Default")
      (node (ref "U$2") (pin "15") (pinfunction "NC7_15") (pintype "bidirectional"))
    )
    (net (code "134") (name "unconnected-(U$2-NC8-Pad16)") (class "Default")
      (node (ref "U$2") (pin "16") (pinfunction "NC8_16") (pintype "bidirectional"))
    )
    (net (code "135") (name "unconnected-(U$2-NC9-Pad17)") (class "Default")
      (node (ref "U$2") (pin "17") (pinfunction "NC9_17") (pintype "bidirectional"))
    )
    (net (code "136") (name "unconnected-(U$2-RESV1-Pad19)") (class "Default")
      (node (ref "U$2") (pin "19") (pinfunction "RESV1_19") (pintype "bidirectional"))
    )
    (net (code "137") (name "unconnected-(U1-P1.4_TB0.1_UCA0STE_A4_C4-Pad17)") (class "Default")
      (node (ref "U1") (pin "17") (pinfunction "P1.4_TB0.1_UCA0STE_A4_C4_17") (pintype "bidirectional"))
    )
    (net (code "138") (name "unconnected-(U1-P1.5_TB0.2_UCA0CLK_A5_C5-Pad18)") (class "Default")
      (node (ref "U1") (pin "18") (pinfunction "P1.5_TB0.2_UCA0CLK_A5_C5_18") (pintype "bidirectional"))
    )
    (net (code "139") (name "unconnected-(U1-P2.2_TB0.2_UCB0CLK-Pad43)") (class "Default")
      (node (ref "U1") (pin "43") (pinfunction "P2.2_TB0.2_UCB0CLK_43") (pintype "bidirectional"))
    )
    (net (code "140") (name "unconnected-(U1-P2.7-Pad62)") (class "Default")
      (node (ref "U1") (pin "62") (pinfunction "P2.7_62") (pintype "bidirectional"))
    )
    (net (code "141") (name "unconnected-(U1-P3.0_A12_C12-Pad4)") (class "Default")
      (node (ref "U1") (pin "4") (pinfunction "P3.0_A12_C12_4") (pintype "bidirectional"))
    )
    (net (code "142") (name "unconnected-(U1-P3.1_A13_C13-Pad5)") (class "Default")
      (node (ref "U1") (pin "5") (pinfunction "P3.1_A13_C13_5") (pintype "bidirectional"))
    )
    (net (code "143") (name "unconnected-(U1-P3.2_A14_C14-Pad6)") (class "Default")
      (node (ref "U1") (pin "6") (pinfunction "P3.2_A14_C14_6") (pintype "bidirectional"))
    )
    (net (code "144") (name "unconnected-(U1-P3.3_A15_C15-Pad7)") (class "Default")
      (node (ref "U1") (pin "7") (pinfunction "P3.3_A15_C15_7") (pintype "bidirectional"))
    )
    (net (code "145") (name "unconnected-(U1-P3.4_TB0.3_SMCLK-Pad47)") (class "Default")
      (node (ref "U1") (pin "47") (pinfunction "P3.4_TB0.3_SMCLK_47") (pintype "bidirectional"))
    )
    (net (code "146") (name "unconnected-(U1-P3.5_TB0.4_COUT-Pad48)") (class "Default")
      (node (ref "U1") (pin "48") (pinfunction "P3.5_TB0.4_COUT_48") (pintype "bidirectional"))
    )
    (net (code "147") (name "unconnected-(U1-P3.6_TB0.5-Pad49)") (class "Default")
      (node (ref "U1") (pin "49") (pinfunction "P3.6_TB0.5_49") (pintype "bidirectional"))
    )
    (net (code "148") (name "unconnected-(U1-P3.7_TB0.6-Pad50)") (class "Default")
      (node (ref "U1") (pin "50") (pinfunction "P3.7_TB0.6_50") (pintype "bidirectional"))
    )
    (net (code "149") (name "unconnected-(U1-P4.0_A8-Pad31)") (class "Default")
      (node (ref "U1") (pin "31") (pinfunction "P4.0_A8_31") (pintype "bidirectional"))
    )
    (net (code "150") (name "unconnected-(U1-P4.1_A9-Pad32)") (class "Default")
      (node (ref "U1") (pin "32") (pinfunction "P4.1_A9_32") (pintype "bidirectional"))
    )
    (net (code "151") (name "unconnected-(U1-P4.2_A10-Pad33)") (class "Default")
      (node (ref "U1") (pin "33") (pinfunction "P4.2_A10_33") (pintype "bidirectional"))
    )
    (net (code "152") (name "unconnected-(U1-P4.3_A11-Pad34)") (class "Default")
      (node (ref "U1") (pin "34") (pinfunction "P4.3_A11_34") (pintype "bidirectional"))
    )
    (net (code "153") (name "unconnected-(U1-P4.4_TB0.5-Pad57)") (class "Default")
      (node (ref "U1") (pin "57") (pinfunction "P4.4_TB0.5_57") (pintype "bidirectional"))
    )
    (net (code "154") (name "unconnected-(U1-P4.5-Pad58)") (class "Default")
      (node (ref "U1") (pin "58") (pinfunction "P4.5_58") (pintype "bidirectional"))
    )
    (net (code "155") (name "unconnected-(U1-P4.6-Pad59)") (class "Default")
      (node (ref "U1") (pin "59") (pinfunction "P4.6_59") (pintype "bidirectional"))
    )
    (net (code "156") (name "unconnected-(U1-P4.7-Pad12)") (class "Default")
      (node (ref "U1") (pin "12") (pinfunction "P4.7_12") (pintype "bidirectional"))
    )
    (net (code "157") (name "unconnected-(U1-P5.0_UCB1SIMO_UCB1SDA-Pad53)") (class "Default")
      (node (ref "U1") (pin "53") (pinfunction "P5.0_UCB1SIMO_UCB1SDA_53") (pintype "bidirectional"))
    )
    (net (code "158") (name "unconnected-(U1-P5.1_UCB1SOMI_UCB1SCL-Pad54)") (class "Default")
      (node (ref "U1") (pin "54") (pinfunction "P5.1_UCB1SOMI_UCB1SCL_54") (pintype "bidirectional"))
    )
    (net (code "159") (name "unconnected-(U1-P5.2_UCB1CLK_TA4CLK-Pad55)") (class "Default")
      (node (ref "U1") (pin "55") (pinfunction "P5.2_UCB1CLK_TA4CLK_55") (pintype "bidirectional"))
    )
    (net (code "160") (name "unconnected-(U1-P5.3_UCB1STE-Pad56)") (class "Default")
      (node (ref "U1") (pin "56") (pinfunction "P5.3_UCB1STE_56") (pintype "bidirectional"))
    )
    (net (code "161") (name "unconnected-(U1-P5.4_UCA2TXD_UCA2SIMO_TB0OUTH-Pad65)") (class "Default")
      (node (ref "U1") (pin "65") (pinfunction "P5.4_UCA2TXD_UCA2SIMO_TB0OUTH_65") (pintype "bidirectional"))
    )
    (net (code "162") (name "unconnected-(U1-P5.5_UCA2RXD_UCA2SOMI_ACLK-Pad66)") (class "Default")
      (node (ref "U1") (pin "66") (pinfunction "P5.5_UCA2RXD_UCA2SOMI_ACLK_66") (pintype "bidirectional"))
    )
    (net (code "163") (name "unconnected-(U1-P5.6_UCA2CLK_TA4.0_SMCLK-Pad67)") (class "Default")
      (node (ref "U1") (pin "67") (pinfunction "P5.6_UCA2CLK_TA4.0_SMCLK_67") (pintype "bidirectional"))
    )
    (net (code "164") (name "unconnected-(U1-P5.7_UCA2STE_TA4.1_MCLK-Pad68)") (class "Default")
      (node (ref "U1") (pin "68") (pinfunction "P5.7_UCA2STE_TA4.1_MCLK_68") (pintype "bidirectional"))
    )
    (net (code "165") (name "unconnected-(U1-P6.0_UCA3TXD_UCA3SIMO-Pad8)") (class "Default")
      (node (ref "U1") (pin "8") (pinfunction "P6.0_UCA3TXD_UCA3SIMO_8") (pintype "bidirectional"))
    )
    (net (code "166") (name "unconnected-(U1-P6.1_UCA3RXD_UCA3SOMI-Pad9)") (class "Default")
      (node (ref "U1") (pin "9") (pinfunction "P6.1_UCA3RXD_UCA3SOMI_9") (pintype "bidirectional"))
    )
    (net (code "167") (name "unconnected-(U1-P6.2_UCA3CLK-Pad10)") (class "Default")
      (node (ref "U1") (pin "10") (pinfunction "P6.2_UCA3CLK_10") (pintype "bidirectional"))
    )
    (net (code "168") (name "unconnected-(U1-P6.3_UCA3STE-Pad11)") (class "Default")
      (node (ref "U1") (pin "11") (pinfunction "P6.3_UCA3STE_11") (pintype "bidirectional"))
    )
    (net (code "169") (name "unconnected-(U1-P6.4_UCB3SIMO_UCB3SDA-Pad69)") (class "Default")
      (node (ref "U1") (pin "69") (pinfunction "P6.4_UCB3SIMO_UCB3SDA_69") (pintype "bidirectional"))
    )
    (net (code "170") (name "unconnected-(U1-P6.5_UCB3SOMI_UCB3SCL-Pad70)") (class "Default")
      (node (ref "U1") (pin "70") (pinfunction "P6.5_UCB3SOMI_UCB3SCL_70") (pintype "bidirectional"))
    )
    (net (code "171") (name "unconnected-(U1-P6.6_UCB3CLK-Pad71)") (class "Default")
      (node (ref "U1") (pin "71") (pinfunction "P6.6_UCB3CLK_71") (pintype "bidirectional"))
    )
    (net (code "172") (name "unconnected-(U1-P6.7_UCB3STE-Pad72)") (class "Default")
      (node (ref "U1") (pin "72") (pinfunction "P6.7_UCB3STE_72") (pintype "bidirectional"))
    )
    (net (code "173") (name "unconnected-(U1-P7.0_UCB2SIMO_UCB2SDA-Pad13)") (class "Default")
      (node (ref "U1") (pin "13") (pinfunction "P7.0_UCB2SIMO_UCB2SDA_13") (pintype "bidirectional"))
    )
    (net (code "174") (name "unconnected-(U1-P7.1_UCB2SOMI_UCB2SCL-Pad14)") (class "Default")
      (node (ref "U1") (pin "14") (pinfunction "P7.1_UCB2SOMI_UCB2SCL_14") (pintype "bidirectional"))
    )
    (net (code "175") (name "unconnected-(U1-P7.2_UCB2CLK-Pad25)") (class "Default")
      (node (ref "U1") (pin "25") (pinfunction "P7.2_UCB2CLK_25") (pintype "bidirectional"))
    )
    (net (code "176") (name "unconnected-(U1-P7.3_UCB2STE_TA4.1-Pad26)") (class "Default")
      (node (ref "U1") (pin "26") (pinfunction "P7.3_UCB2STE_TA4.1_26") (pintype "bidirectional"))
    )
    (net (code "177") (name "unconnected-(U1-P7.4__TA4.0_A16-Pad27)") (class "Default")
      (node (ref "U1") (pin "27") (pinfunction "P7.4__TA4.0_A16_27") (pintype "bidirectional"))
    )
    (net (code "178") (name "unconnected-(U1-P7.5_A17-Pad28)") (class "Default")
      (node (ref "U1") (pin "28") (pinfunction "P7.5_A17_28") (pintype "bidirectional"))
    )
    (net (code "179") (name "unconnected-(U1-P7.6_A18-Pad29)") (class "Default")
      (node (ref "U1") (pin "29") (pinfunction "P7.6_A18_29") (pintype "bidirectional"))
    )
    (net (code "180") (name "unconnected-(U1-P7.7_A19-Pad30)") (class "Default")
      (node (ref "U1") (pin "30") (pinfunction "P7.7_A19_30") (pintype "bidirectional"))
    )
    (net (code "181") (name "unconnected-(U1-P8.0-Pad15)") (class "Default")
      (node (ref "U1") (pin "15") (pinfunction "P8.0_15") (pintype "bidirectional"))
    )
    (net (code "182") (name "unconnected-(U1-P8.1-Pad44)") (class "Default")
      (node (ref "U1") (pin "44") (pinfunction "P8.1_44") (pintype "bidirectional"))
    )
    (net (code "183") (name "unconnected-(U1-P8.2-Pad45)") (class "Default")
      (node (ref "U1") (pin "45") (pinfunction "P8.2_45") (pintype "bidirectional"))
    )
    (net (code "184") (name "unconnected-(U1-P8.3-Pad46)") (class "Default")
      (node (ref "U1") (pin "46") (pinfunction "P8.3_46") (pintype "bidirectional"))
    )
    (net (code "185") (name "unconnected-(U1-PJ.0_TDO_TB0OUTH_SMCLK_SRSCG1_C6-Pad21)") (class "Default")
      (node (ref "U1") (pin "21") (pinfunction "PJ.0_TDO_TB0OUTH_SMCLK_SRSCG1_C6_21") (pintype "bidirectional"))
    )
    (net (code "186") (name "unconnected-(U1-PJ.1_TDI_TCLK_MCLK_SRSCG0_C7-Pad22)") (class "Default")
      (node (ref "U1") (pin "22") (pinfunction "PJ.1_TDI_TCLK_MCLK_SRSCG0_C7_22") (pintype "bidirectional"))
    )
    (net (code "187") (name "unconnected-(U1-PJ.2_TMS_ACLK_SROSCOFF_C8-Pad23)") (class "Default")
      (node (ref "U1") (pin "23") (pinfunction "PJ.2_TMS_ACLK_SROSCOFF_C8_23") (pintype "bidirectional"))
    )
    (net (code "188") (name "unconnected-(U1-PJ.3_TCK_SRCPUOFF_C9-Pad24)") (class "Default")
      (node (ref "U1") (pin "24") (pinfunction "PJ.3_TCK_SRCPUOFF_C9_24") (pintype "bidirectional"))
    )
    (net (code "189") (name "unconnected-(U1-PJ.4_LFXIN-Pad77)") (class "Default")
      (node (ref "U1") (pin "77") (pinfunction "PJ.4_LFXIN_77") (pintype "bidirectional"))
    )
    (net (code "190") (name "unconnected-(U1-PJ.6_HFXIN-Pad74)") (class "Default")
      (node (ref "U1") (pin "74") (pinfunction "PJ.6_HFXIN_74") (pintype "bidirectional"))
    )
    (net (code "191") (name "unconnected-(U1-TEST_SBWTCK-Pad37)") (class "Default")
      (node (ref "U1") (pin "37") (pinfunction "TEST_SBWTCK_37") (pintype "input"))
    )
  )
)
